# BrushlessDrive.net
KiCad netlist of a schematic drawn in Altium Designer
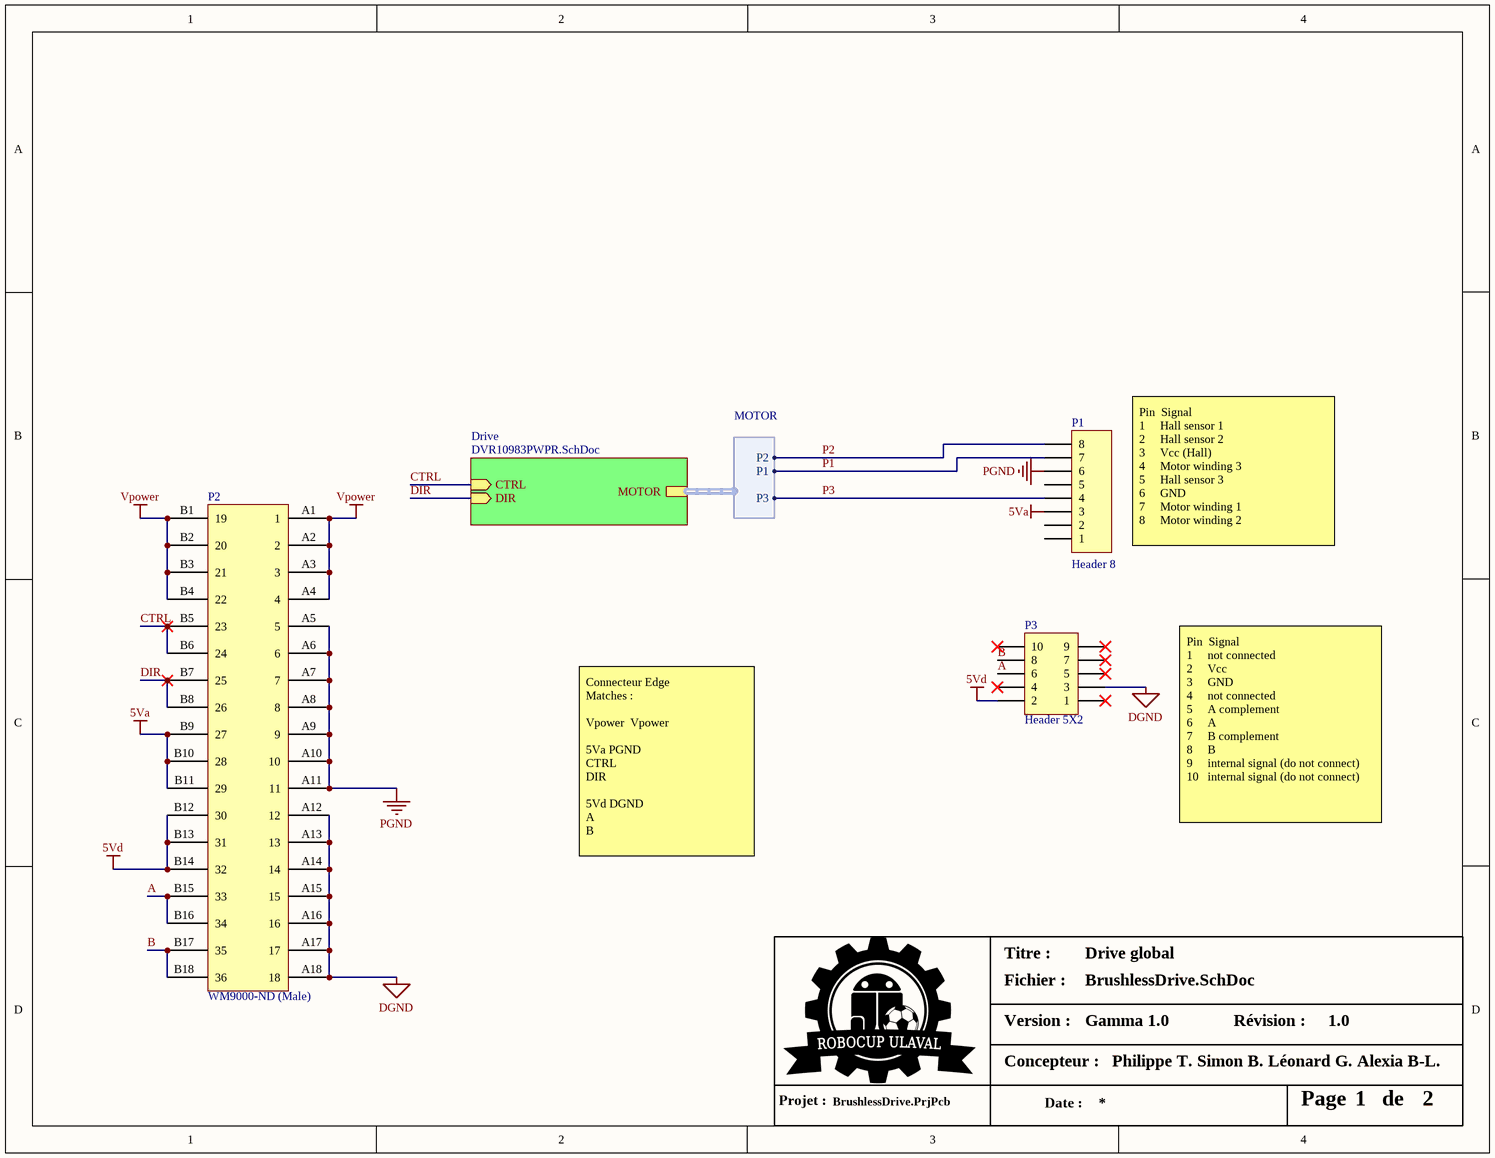
[diagram p0: BrushlessDrive.SchDoc]

(export (version "E")
  (design (tool "Eeschema 10.0.6"))
  (components
    (comp (ref "P1")
      (value "Header 8")
      (footprint "HallSensor Connector")
      (description "Header, 8-Pin")
      (fields (field (name "PUBLISHER") "Altium Limited"))
      (libsource (lib "Miscellaneous Connectors") (part "Header 8"))
    )
    (comp (ref "P2")
      (value "WM9000-ND (Male)")
      (footprint "Edge connector 36Pos")
      (libsource (lib "BrushlessDrive") (part "WM9000-ND (Male)"))
    )
    (comp (ref "P3")
      (value "Header 5X2")
      (footprint "Encoder Connector")
      (description "Header, 5-Pin, Dual row")
      (fields (field (name "PUBLISHER") "Altium Limited"))
      (libsource (lib "Miscellaneous Connectors") (part "Header 5X2"))
    )
  )
  (nets
    (net (code "2") (name "/A") (class "Default")
      (node (ref "P2") (pin "B15") (pinfunction "33_B15") (pintype "passive"))
      (node (ref "P2") (pin "B16") (pinfunction "34_B16") (pintype "passive"))
      (node (ref "P3") (pin "6") (pinfunction "6_6") (pintype "passive"))
    )
    (net (code "3") (name "/B") (class "Default")
      (node (ref "P2") (pin "B17") (pinfunction "35_B17") (pintype "passive"))
      (node (ref "P2") (pin "B18") (pinfunction "36_B18") (pintype "passive"))
      (node (ref "P3") (pin "8") (pinfunction "8_8") (pintype "passive"))
    )
    (net (code "4") (name "/CTRL") (class "Default")
      (node (ref "P2") (pin "B5") (pinfunction "23_B5") (pintype "passive"))
      (node (ref "P2") (pin "B6") (pinfunction "24_B6") (pintype "passive"))
    )
    (net (code "5") (name "/DIR") (class "Default")
      (node (ref "P2") (pin "B7") (pinfunction "25_B7") (pintype "passive"))
      (node (ref "P2") (pin "B8") (pinfunction "26_B8") (pintype "passive"))
    )
    (net (code "6") (name "/P1") (class "Default")
      (node (ref "P1") (pin "7") (pinfunction "7_7") (pintype "passive"))
    )
    (net (code "7") (name "/P2") (class "Default")
      (node (ref "P1") (pin "8") (pinfunction "8_8") (pintype "passive"))
    )
    (net (code "8") (name "/P3") (class "Default")
      (node (ref "P1") (pin "4") (pinfunction "4_4") (pintype "passive"))
    )
    (net (code "10") (name "5Va") (class "Default")
      (node (ref "P1") (pin "3") (pinfunction "3_3") (pintype "passive"))
      (node (ref "P2") (pin "B10") (pinfunction "28_B10") (pintype "passive"))
      (node (ref "P2") (pin "B11") (pinfunction "29_B11") (pintype "passive"))
      (node (ref "P2") (pin "B9") (pinfunction "27_B9") (pintype "passive"))
    )
    (net (code "11") (name "5Vd") (class "Default")
      (node (ref "P2") (pin "B12") (pinfunction "30_B12") (pintype "passive"))
      (node (ref "P2") (pin "B13") (pinfunction "31_B13") (pintype "passive"))
      (node (ref "P2") (pin "B14") (pinfunction "32_B14") (pintype "passive"))
      (node (ref "P3") (pin "2") (pinfunction "2_2") (pintype "passive"))
    )
    (net (code "12") (name "DGND") (class "Default")
      (node (ref "P2") (pin "A12") (pinfunction "12_A12") (pintype "passive"))
      (node (ref "P2") (pin "A13") (pinfunction "13_A13") (pintype "passive"))
      (node (ref "P2") (pin "A14") (pinfunction "14_A14") (pintype "passive"))
      (node (ref "P2") (pin "A15") (pinfunction "15_A15") (pintype "passive"))
      (node (ref "P2") (pin "A16") (pinfunction "16_A16") (pintype "passive"))
      (node (ref "P2") (pin "A17") (pinfunction "17_A17") (pintype "passive"))
      (node (ref "P2") (pin "A18") (pinfunction "18_A18") (pintype "passive"))
      (node (ref "P3") (pin "3") (pinfunction "3_3") (pintype "passive"))
    )
    (net (code "13") (name "PGND") (class "Default")
      (node (ref "P1") (pin "6") (pinfunction "6_6") (pintype "passive"))
      (node (ref "P2") (pin "A10") (pinfunction "10_A10") (pintype "passive"))
      (node (ref "P2") (pin "A11") (pinfunction "11_A11") (pintype "passive"))
      (node (ref "P2") (pin "A5") (pinfunction "5_A5") (pintype "passive"))
      (node (ref "P2") (pin "A6") (pinfunction "6_A6") (pintype "passive"))
      (node (ref "P2") (pin "A7") (pinfunction "7_A7") (pintype "passive"))
      (node (ref "P2") (pin "A8") (pinfunction "8_A8") (pintype "passive"))
      (node (ref "P2") (pin "A9") (pinfunction "9_A9") (pintype "passive"))
    )
    (net (code "14") (name "Vpower") (class "Default")
      (node (ref "P2") (pin "A1") (pinfunction "1_A1") (pintype "passive"))
      (node (ref "P2") (pin "A2") (pinfunction "2_A2") (pintype "passive"))
      (node (ref "P2") (pin "A3") (pinfunction "3_A3") (pintype "passive"))
      (node (ref "P2") (pin "A4") (pinfunction "4_A4") (pintype "passive"))
      (node (ref "P2") (pin "B1") (pinfunction "19_B1") (pintype "passive"))
      (node (ref "P2") (pin "B2") (pinfunction "20_B2") (pintype "passive"))
      (node (ref "P2") (pin "B3") (pinfunction "21_B3") (pintype "passive"))
      (node (ref "P2") (pin "B4") (pinfunction "22_B4") (pintype "passive"))
    )
    (net (code "15") (name "unconnected-(P1-Pad1)") (class "Default")
      (node (ref "P1") (pin "1") (pinfunction "1_1") (pintype "passive"))
    )
    (net (code "16") (name "unconnected-(P1-Pad2)") (class "Default")
      (node (ref "P1") (pin "2") (pinfunction "2_2") (pintype "passive"))
    )
    (net (code "17") (name "unconnected-(P1-Pad5)") (class "Default")
      (node (ref "P1") (pin "5") (pinfunction "5_5") (pintype "passive"))
    )
    (net (code "18") (name "unconnected-(P3-Pad1)") (class "Default")
      (node (ref "P3") (pin "1") (pinfunction "1_1") (pintype "passive+no_connect"))
    )
    (net (code "19") (name "unconnected-(P3-Pad4)") (class "Default")
      (node (ref "P3") (pin "4") (pinfunction "4_4") (pintype "passive+no_connect"))
    )
    (net (code "20") (name "unconnected-(P3-Pad5)") (class "Default")
      (node (ref "P3") (pin "5") (pinfunction "5_5") (pintype "passive+no_connect"))
    )
    (net (code "21") (name "unconnected-(P3-Pad7)") (class "Default")
      (node (ref "P3") (pin "7") (pinfunction "7_7") (pintype "passive+no_connect"))
    )
    (net (code "22") (name "unconnected-(P3-Pad9)") (class "Default")
      (node (ref "P3") (pin "9") (pinfunction "9_9") (pintype "passive+no_connect"))
    )
    (net (code "23") (name "unconnected-(P3-Pad10)") (class "Default")
      (node (ref "P3") (pin "10") (pinfunction "10_10") (pintype "passive+no_connect"))
    )
  )
)
